# Interface_Mikrobus.net
KiCad netlist of a schematic drawn in Altium Designer
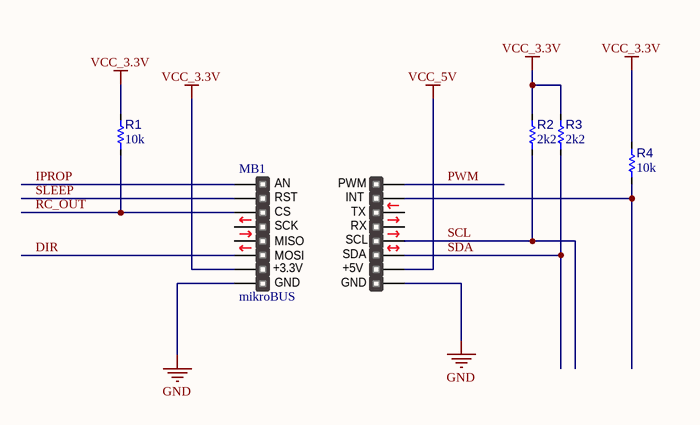
[diagram p0: Interface_Mikrobus.SchDoc]

(export (version "E")
  (design (tool "Eeschema 10.0.6"))
  (components
    (comp (ref "MB1")
      (value "mikroBUS")
      (footprint "mikroBUS - Large")
      (description "mikroBUS compatible add-on board")
      (libsource (lib "mikroBUS_Add-on_standard") (part "mikroBUS compatible add-on board"))
    )
    (comp (ref "R1")
      (value "10k")
      (footprint "R_1005[0402]")
      (description "Resistor type 1")
      (fields (field (name "TOLERANCE") "1%") (field (name "Comment") "Res 10k 1% 0402"))
      (libsource (lib "TEP_243-Altium_DBLib") (part "resistor"))
    )
    (comp (ref "R2")
      (value "2k2")
      (footprint "R_1005[0402]")
      (description "Resistor type 1")
      (fields (field (name "TOLERANCE") "1%") (field (name "Comment") "Res 2k2 1% 0402"))
      (libsource (lib "TEP_243-Altium_DBLib") (part "resistor"))
    )
    (comp (ref "R3")
      (value "2k2")
      (footprint "R_1005[0402]")
      (description "Resistor type 1")
      (fields (field (name "TOLERANCE") "1%") (field (name "Comment") "Res 2k2 1% 0402"))
      (libsource (lib "TEP_243-Altium_DBLib") (part "resistor"))
    )
    (comp (ref "R4")
      (value "10k")
      (footprint "R_1005[0402]")
      (description "Resistor type 1")
      (fields (field (name "TOLERANCE") "1%") (field (name "Comment") "Res 10k 1% 0402"))
      (libsource (lib "TEP_243-Altium_DBLib") (part "resistor"))
    )
  )
  (nets
    (net (code "1") (name "/DIR") (class "Default")
      (node (ref "MB1") (pin "6") (pinfunction "MOSI_6") (pintype "passive"))
    )
    (net (code "2") (name "/IPROP") (class "Default")
      (node (ref "MB1") (pin "1") (pinfunction "AN_1") (pintype "passive"))
    )
    (net (code "3") (name "/PWM") (class "Default")
      (node (ref "MB1") (pin "16") (pinfunction "PWM_16") (pintype "passive"))
    )
    (net (code "4") (name "/RC_OUT") (class "Default")
      (node (ref "MB1") (pin "3") (pinfunction "CS_3") (pintype "passive"))
      (node (ref "R1") (pin "1") (pinfunction "1_1") (pintype "passive"))
    )
    (net (code "5") (name "/SCL") (class "Default")
      (node (ref "MB1") (pin "12") (pinfunction "SCL_12") (pintype "passive"))
      (node (ref "R2") (pin "1") (pinfunction "1_1") (pintype "passive"))
    )
    (net (code "6") (name "/SDA") (class "Default")
      (node (ref "MB1") (pin "11") (pinfunction "SDA_11") (pintype "passive"))
      (node (ref "R3") (pin "1") (pinfunction "1_1") (pintype "passive"))
    )
    (net (code "7") (name "/SLEEP") (class "Default")
      (node (ref "MB1") (pin "2") (pinfunction "RST_2") (pintype "passive"))
    )
    (net (code "8") (name "GND") (class "Default")
      (node (ref "MB1") (pin "8") (pinfunction "GND_8") (pintype "passive"))
      (node (ref "MB1") (pin "9") (pinfunction "GND_9") (pintype "passive"))
    )
    (net (code "9") (name "Net-(MB1-INT)") (class "Default")
      (node (ref "MB1") (pin "15") (pinfunction "INT_15") (pintype "passive"))
      (node (ref "R4") (pin "1") (pinfunction "1_1") (pintype "passive"))
    )
    (net (code "10") (name "VCC_3.3V") (class "Default")
      (node (ref "MB1") (pin "7") (pinfunction "3.3V_7") (pintype "passive"))
      (node (ref "R1") (pin "2") (pinfunction "2_2") (pintype "passive"))
      (node (ref "R2") (pin "2") (pinfunction "2_2") (pintype "passive"))
      (node (ref "R3") (pin "2") (pinfunction "2_2") (pintype "passive"))
      (node (ref "R4") (pin "2") (pinfunction "2_2") (pintype "passive"))
    )
    (net (code "11") (name "VCC_5V") (class "Default")
      (node (ref "MB1") (pin "10") (pinfunction "5V_10") (pintype "passive"))
    )
    (net (code "12") (name "unconnected-(MB1-MISO-Pad5)") (class "Default")
      (node (ref "MB1") (pin "5") (pinfunction "MISO_5") (pintype "passive"))
    )
    (net (code "13") (name "unconnected-(MB1-RX-Pad14)") (class "Default")
      (node (ref "MB1") (pin "14") (pinfunction "RX_14") (pintype "passive"))
    )
    (net (code "14") (name "unconnected-(MB1-SCK-Pad4)") (class "Default")
      (node (ref "MB1") (pin "4") (pinfunction "SCK_4") (pintype "passive"))
    )
    (net (code "15") (name "unconnected-(MB1-TX-Pad13)") (class "Default")
      (node (ref "MB1") (pin "13") (pinfunction "TX_13") (pintype "passive"))
    )
  )
)
